# Integrator.net
KiCad netlist of a schematic drawn in Altium Designer
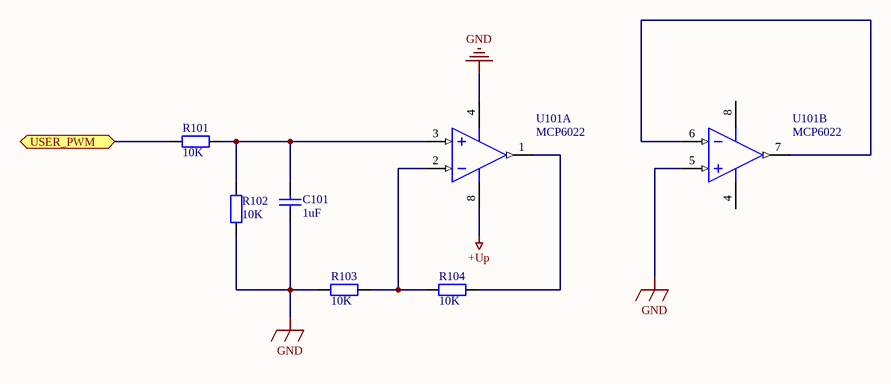
[diagram p0: Integrator.SchDoc]

(export (version "E")
  (design (tool "Eeschema 10.0.6"))
  (components
    (comp (ref "C101")
      (value "1uF")
      (footprint "0805")
      (description "Capacitor")
      (fields (field (name "PUBLISHER") "Altium Limited"))
      (libsource (lib "Quasar ARM") (part "Capacitor SMD"))
    )
    (comp (ref "R101")
      (value "10K")
      (footprint "1206_SMD_Resistor")
      (description "Resistor")
      (fields (field (name "PUBLISHER") "Dmitry Kuzmin"))
      (libsource (lib "") (part "Resistor_1"))
    )
    (comp (ref "R102")
      (value "10K")
      (footprint "1206_SMD_Resistor")
      (description "Resistor")
      (fields (field (name "PUBLISHER") "Dmitry Kuzmin"))
      (libsource (lib "Quasar ARM") (part "Resistor"))
    )
    (comp (ref "R103")
      (value "10K")
      (footprint "1206_SMD_Resistor")
      (description "Resistor")
      (fields (field (name "PUBLISHER") "Dmitry Kuzmin"))
      (libsource (lib "") (part "Resistor_1"))
    )
    (comp (ref "R104")
      (value "10K")
      (footprint "1206_SMD_Resistor")
      (description "Resistor")
      (fields (field (name "PUBLISHER") "Dmitry Kuzmin"))
      (libsource (lib "") (part "Resistor_1"))
    )
    (comp (ref "U101")
      (value "MCP6022")
      (footprint "SOIC-SN8_N")
      (description "Rail-to-Rail Input/Output, 10 MHz Operational Amplifier, 8-Pin SOIC, Industrial Temperature")
      (fields (field (name "PUBLISHER") "Altium Limited"))
      (libsource (lib "Quasar ARM") (part "MCP6022-I/SN"))
    )
  )
  (nets
    (net (code "1") (name "+Up") (class "Default")
      (node (ref "U101") (pin "8") (pinfunction "VDD_8") (pintype "power_in"))
    )
    (net (code "2") (name "/USER_PWM") (class "Default")
      (node (ref "R101") (pin "1") (pinfunction "1_1") (pintype "passive"))
    )
    (net (code "3") (name "GND") (class "Default")
      (node (ref "C101") (pin "1") (pinfunction "1_1") (pintype "passive"))
      (node (ref "R102") (pin "1") (pinfunction "1_1") (pintype "passive"))
      (node (ref "R103") (pin "1") (pinfunction "1_1") (pintype "passive"))
      (node (ref "U101") (pin "4") (pinfunction "VSS_4") (pintype "power_in"))
      (node (ref "U101") (pin "5") (pinfunction "VINB+_5") (pintype "input"))
    )
    (net (code "4") (name "Net-(U101A-VINA+)") (class "Default")
      (node (ref "C101") (pin "2") (pinfunction "2_2") (pintype "passive"))
      (node (ref "R101") (pin "2") (pinfunction "2_2") (pintype "passive"))
      (node (ref "R102") (pin "2") (pinfunction "2_2") (pintype "passive"))
      (node (ref "U101") (pin "3") (pinfunction "VINA+_3") (pintype "input"))
    )
    (net (code "5") (name "Net-(U101A-VINA-)") (class "Default")
      (node (ref "R103") (pin "2") (pinfunction "2_2") (pintype "passive"))
      (node (ref "R104") (pin "1") (pinfunction "1_1") (pintype "passive"))
      (node (ref "U101") (pin "2") (pinfunction "VINA-_2") (pintype "input"))
    )
    (net (code "6") (name "Net-(U101A-VOUTA)") (class "Default")
      (node (ref "R104") (pin "2") (pinfunction "2_2") (pintype "passive"))
      (node (ref "U101") (pin "1") (pinfunction "VOUTA_1") (pintype "output"))
    )
    (net (code "7") (name "Net-(U101B-VINB-)") (class "Default")
      (node (ref "U101") (pin "6") (pinfunction "VINB-_6") (pintype "input"))
      (node (ref "U101") (pin "7") (pinfunction "VOUTB_7") (pintype "output"))
    )
    (net (code "8") (name "unconnected-(U101B-VDD-Pad8)") (class "Default")
      (node (ref "U101") (pin "8") (pinfunction "VDD_8") (pintype "power_in"))
    )
    (net (code "9") (name "unconnected-(U101B-VSS-Pad4)") (class "Default")
      (node (ref "U101") (pin "4") (pinfunction "VSS_4") (pintype "power_in"))
    )
  )
)
